# hi_min_subsystem.net
KiCad netlist of a schematic drawn in EAGLE
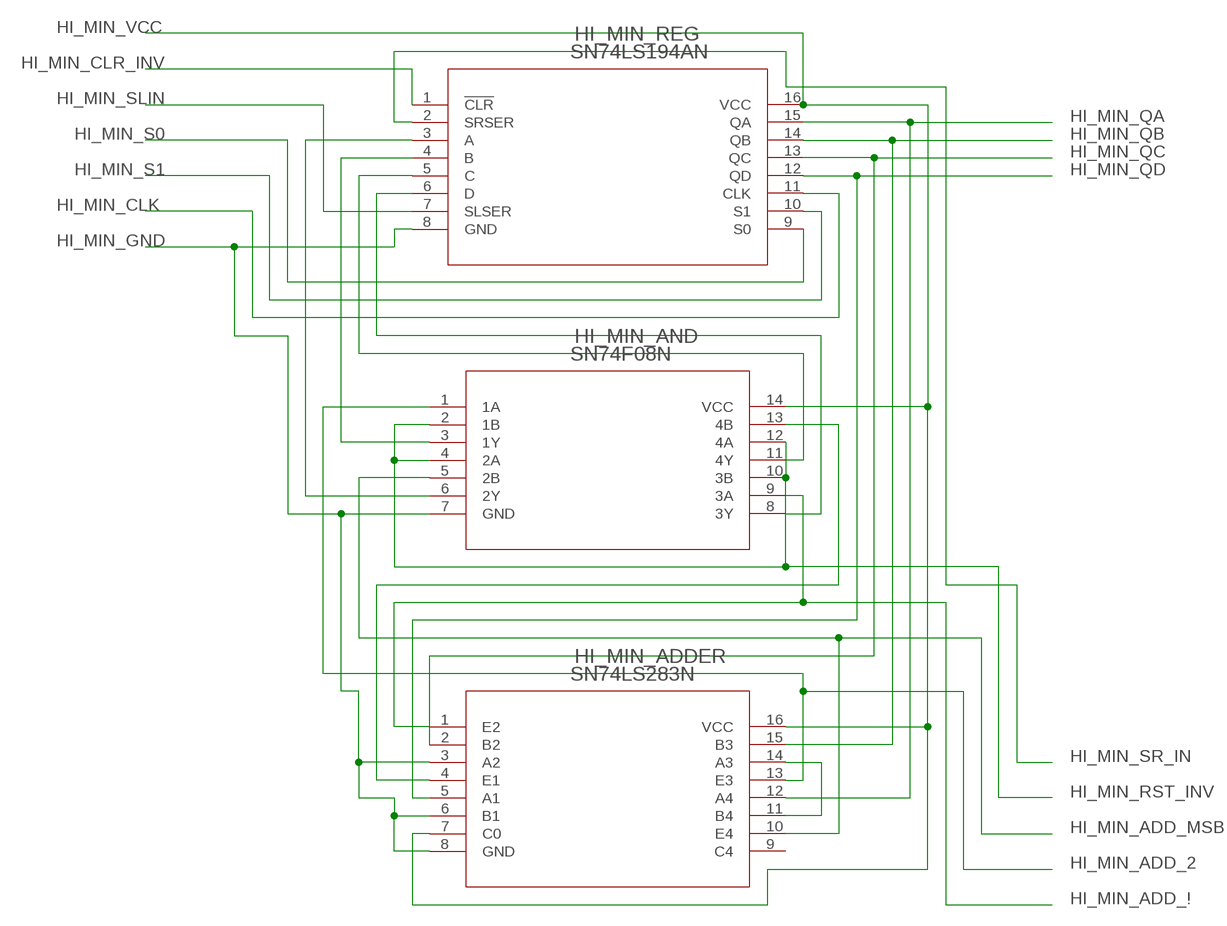
[diagram p0: schematic, sheet 1]

(export (version "E")
  (design (tool "Eeschema 10.0.6"))
  (components
    (comp (ref "HI_MIN_ADDER")
      (value "SN74LS283N")
      (footprint "eagle-import:N16")
      (fields
        (field (name "GENERIC_PART_NUMBER") "SN74LS283")
        (field (name "MANUFACTURER") "Texas Instruments")
      )
      (libsource (lib "eagle-import") (part "SN74LS283N"))
    )
    (comp (ref "HI_MIN_AND")
      (value "SN74F08N")
      (footprint "eagle-import:N14")
      (fields
        (field (name "GENERIC_PART_NUMBER") "SN74F08")
        (field (name "MANUFACTURER") "Texas Instruments")
      )
      (libsource (lib "eagle-import") (part "SN74F08N"))
    )
    (comp (ref "HI_MIN_REG")
      (value "SN74LS194AN")
      (footprint "eagle-import:N16")
      (fields
        (field (name "GENERIC_PART_NUMBER") "SN74LS194A")
        (field (name "MANUFACTURER") "Texas Instruments")
      )
      (libsource (lib "eagle-import") (part "SN74LS194AN"))
    )
  )
  (nets
    (net (code "1") (name "/HI_MIN_ADD_2") (class "Default")
      (node (ref "HI_MIN_ADDER") (pin "13") (pinfunction "E3_13") (pintype "output"))
      (node (ref "HI_MIN_AND") (pin "1") (pinfunction "1A_1") (pintype "input"))
    )
    (net (code "2") (name "/HI_MIN_ADD_MSB") (class "Default")
      (node (ref "HI_MIN_ADDER") (pin "10") (pinfunction "E4_10") (pintype "output"))
      (node (ref "HI_MIN_AND") (pin "5") (pinfunction "2B_5") (pintype "input"))
    )
    (net (code "3") (name "/HI_MIN_ADD_~{}") (class "Default")
      (node (ref "HI_MIN_ADDER") (pin "1") (pinfunction "E2_1") (pintype "output"))
      (node (ref "HI_MIN_AND") (pin "9") (pinfunction "3A_9") (pintype "input"))
    )
    (net (code "4") (name "/HI_MIN_CLK") (class "Default")
      (node (ref "HI_MIN_REG") (pin "11") (pinfunction "CLK_11") (pintype "input"))
    )
    (net (code "5") (name "/HI_MIN_CLR_INV") (class "Default")
      (node (ref "HI_MIN_REG") (pin "1") (pinfunction "~{CLR}_1") (pintype "input"))
    )
    (net (code "6") (name "/HI_MIN_GND") (class "Default")
      (node (ref "HI_MIN_ADDER") (pin "3") (pinfunction "A2_3") (pintype "input"))
      (node (ref "HI_MIN_ADDER") (pin "6") (pinfunction "B1_6") (pintype "input"))
      (node (ref "HI_MIN_ADDER") (pin "8") (pinfunction "GND_8") (pintype "power_in"))
      (node (ref "HI_MIN_AND") (pin "7") (pinfunction "GND_7") (pintype "power_in"))
      (node (ref "HI_MIN_REG") (pin "8") (pinfunction "GND_8") (pintype "power_in"))
    )
    (net (code "7") (name "/HI_MIN_QA") (class "Default")
      (node (ref "HI_MIN_ADDER") (pin "12") (pinfunction "A4_12") (pintype "input"))
      (node (ref "HI_MIN_REG") (pin "15") (pinfunction "QA_15") (pintype "output"))
    )
    (net (code "8") (name "/HI_MIN_QB") (class "Default")
      (node (ref "HI_MIN_ADDER") (pin "15") (pinfunction "B3_15") (pintype "input"))
      (node (ref "HI_MIN_REG") (pin "14") (pinfunction "QB_14") (pintype "output"))
    )
    (net (code "9") (name "/HI_MIN_QC") (class "Default")
      (node (ref "HI_MIN_ADDER") (pin "2") (pinfunction "B2_2") (pintype "input"))
      (node (ref "HI_MIN_REG") (pin "13") (pinfunction "QC_13") (pintype "output"))
    )
    (net (code "10") (name "/HI_MIN_QD") (class "Default")
      (node (ref "HI_MIN_ADDER") (pin "5") (pinfunction "A1_5") (pintype "input"))
      (node (ref "HI_MIN_REG") (pin "12") (pinfunction "QD_12") (pintype "output"))
    )
    (net (code "11") (name "/HI_MIN_RST_INV") (class "Default")
      (node (ref "HI_MIN_AND") (pin "10") (pinfunction "3B_10") (pintype "input"))
      (node (ref "HI_MIN_AND") (pin "12") (pinfunction "4A_12") (pintype "input"))
      (node (ref "HI_MIN_AND") (pin "2") (pinfunction "1B_2") (pintype "input"))
      (node (ref "HI_MIN_AND") (pin "4") (pinfunction "2A_4") (pintype "input"))
    )
    (net (code "12") (name "/HI_MIN_S0") (class "Default")
      (node (ref "HI_MIN_REG") (pin "9") (pinfunction "S0_9") (pintype "input"))
    )
    (net (code "13") (name "/HI_MIN_S1") (class "Default")
      (node (ref "HI_MIN_REG") (pin "10") (pinfunction "S1_10") (pintype "input"))
    )
    (net (code "14") (name "/HI_MIN_SLIN") (class "Default")
      (node (ref "HI_MIN_REG") (pin "7") (pinfunction "SLSER_7") (pintype "input"))
    )
    (net (code "15") (name "/HI_MIN_SR_IN") (class "Default")
      (node (ref "HI_MIN_REG") (pin "2") (pinfunction "SRSER_2") (pintype "input"))
    )
    (net (code "16") (name "/HI_MIN_VCC") (class "Default")
      (node (ref "HI_MIN_ADDER") (pin "16") (pinfunction "VCC_16") (pintype "power_in"))
      (node (ref "HI_MIN_ADDER") (pin "7") (pinfunction "C0_7") (pintype "input"))
      (node (ref "HI_MIN_AND") (pin "14") (pinfunction "VCC_14") (pintype "power_in"))
      (node (ref "HI_MIN_REG") (pin "16") (pinfunction "VCC_16") (pintype "power_in"))
    )
    (net (code "17") (name "Net-(HI_MIN_ADDER-A3)") (class "Default")
      (node (ref "HI_MIN_ADDER") (pin "11") (pinfunction "B4_11") (pintype "input"))
      (node (ref "HI_MIN_ADDER") (pin "14") (pinfunction "A3_14") (pintype "input"))
    )
    (net (code "18") (name "Net-(HI_MIN_ADDER-E1)") (class "Default")
      (node (ref "HI_MIN_ADDER") (pin "4") (pinfunction "E1_4") (pintype "output"))
      (node (ref "HI_MIN_AND") (pin "13") (pinfunction "4B_13") (pintype "input"))
    )
    (net (code "19") (name "Net-(HI_MIN_AND-1Y)") (class "Default")
      (node (ref "HI_MIN_AND") (pin "3") (pinfunction "1Y_3") (pintype "output"))
      (node (ref "HI_MIN_REG") (pin "4") (pinfunction "B_4") (pintype "input"))
    )
    (net (code "20") (name "Net-(HI_MIN_AND-2Y)") (class "Default")
      (node (ref "HI_MIN_AND") (pin "6") (pinfunction "2Y_6") (pintype "output"))
      (node (ref "HI_MIN_REG") (pin "3") (pinfunction "A_3") (pintype "input"))
    )
    (net (code "21") (name "Net-(HI_MIN_AND-3Y)") (class "Default")
      (node (ref "HI_MIN_AND") (pin "8") (pinfunction "3Y_8") (pintype "output"))
      (node (ref "HI_MIN_REG") (pin "6") (pinfunction "D_6") (pintype "input"))
    )
    (net (code "22") (name "Net-(HI_MIN_AND-4Y)") (class "Default")
      (node (ref "HI_MIN_AND") (pin "11") (pinfunction "4Y_11") (pintype "output"))
      (node (ref "HI_MIN_REG") (pin "5") (pinfunction "C_5") (pintype "input"))
    )
    (net (code "23") (name "unconnected-(HI_MIN_ADDER-C4-Pad9)") (class "Default")
      (node (ref "HI_MIN_ADDER") (pin "9") (pinfunction "C4_9") (pintype "input"))
    )
  )
)
